# Power_Isolation.net
KiCad netlist of a schematic drawn in Altium Designer
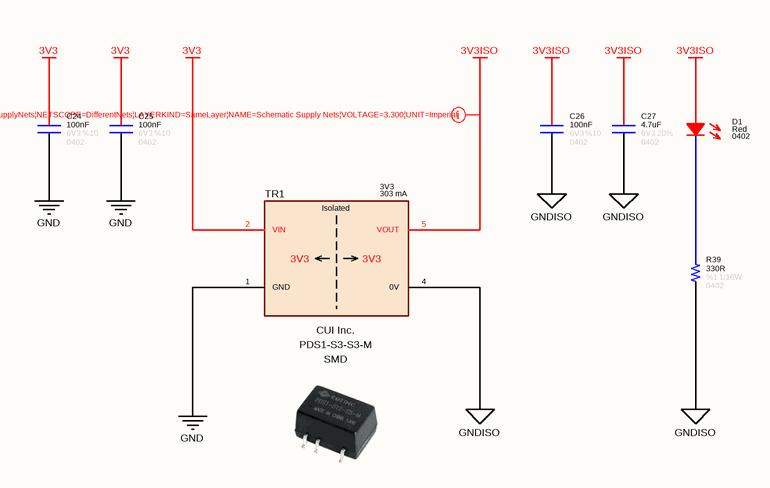
[diagram p0: Power Isolation.SchDoc]

(export (version "E")
  (design (tool "Eeschema 10.0.6"))
  (components
    (comp (ref "C24")
      (value "100nF")
      (footprint "CAPACITOR_0402")
      (description "Capacitor - 100nF [0402-6V3] (Ceramic)")
      (fields
        (field (name "MANUFACTURER PART NUMBER") "04026D104KAT4A")
        (field (name "TOLERANCE") "%10")
        (field (name "VOLTAGE") "6V3")
        (field (name "CASE") "0402")
        (field (name "Comment") "Capacitor - 100nF [0402] (Ceramic)")
      )
      (libsource (lib "Akkoyun") (part "Capacitor - 100nF [0402-6V3]"))
    )
    (comp (ref "C25")
      (value "100nF")
      (footprint "CAPACITOR_0402")
      (description "Capacitor - 100nF [0402-6V3] (Ceramic)")
      (fields
        (field (name "MANUFACTURER PART NUMBER") "04026D104KAT4A")
        (field (name "TOLERANCE") "%10")
        (field (name "VOLTAGE") "6V3")
        (field (name "CASE") "0402")
        (field (name "Comment") "Capacitor - 100nF [0402] (Ceramic)")
      )
      (libsource (lib "Akkoyun") (part "Capacitor - 100nF [0402-6V3]"))
    )
    (comp (ref "C26")
      (value "100nF")
      (footprint "CAPACITOR_0402")
      (description "Capacitor - 100nF [0402-6V3] (Ceramic)")
      (fields
        (field (name "MANUFACTURER PART NUMBER") "04026D104KAT4A")
        (field (name "TOLERANCE") "%10")
        (field (name "VOLTAGE") "6V3")
        (field (name "CASE") "0402")
        (field (name "Comment") "Capacitor - 100nF [0402] (Ceramic)")
      )
      (libsource (lib "Akkoyun") (part "Capacitor - 100nF [0402-6V3]"))
    )
    (comp (ref "C27")
      (value "4.7uF")
      (footprint "CAPACITOR_0402")
      (description "Multilayer Ceramic Capacitors - SMD - 6V3 4.7uF X5R 0402 20%")
      (fields
        (field (name "MANUFACTURER PART NUMBER") "C0402C475M9PACTU")
        (field (name "TOLERANCE") "20%")
        (field (name "CASE") "0402")
        (field (name "VOLTAGE") "6V3")
        (field (name "Comment") "Capacitor - 4.7uF [0402] (Ceramic)")
      )
      (libsource (lib "Akkoyun") (part "Capacitor - 4.7uF [0402-6V3]"))
    )
    (comp (ref "D1")
      (value "SMD LED (Red)")
      (footprint "LED_0402")
      (description "Standard LEDs - SMD MINI-MOLD ULTRA COMPACT RED")
      (fields
        (field (name "MANUFACTURER PART NUMBER") "SML-P12VTT86R")
        (field (name "CASE") "0402")
        (field (name "COLOR") "Red")
      )
      (libsource (lib "Akkoyun") (part "Diode - LED (0402-Red)"))
    )
    (comp (ref "R39")
      (value "330R")
      (footprint "RESISTOR_0402")
      (description "Thick Film Resistors - SMD 1/16 W 330 Ohm 1%")
      (fields
        (field (name "MANUFACTURER PART NUMBER") "CRCW0402330RFKED")
        (field (name "CASE") "0402")
        (field (name "TOLERANCE") "%1")
        (field (name "POWER") "1/16W")
        (field (name "Comment") "330R - 0402 - %1 - 1/16W")
      )
      (libsource (lib "Akkoyun") (part "Resistor - 330R [0402]"))
    )
    (comp (ref "TR1")
      (value "PDS1-S3-S3-M")
      (footprint "PDS1-Sx-Sx-M")
      (description "Module DC-DC 3.3VIN 1-OUT 3.3V 0.303A 1W 5-Pin SMD Module")
      (fields
        (field (name "OUTPUT CURRENT") "303 mA")
        (field (name "OUTPUT VOLTAGE") "3V3")
        (field (name "MANUFACTURER NAME") "CUI Inc.")
        (field (name "MANUFACTURER PART NUMBER") "PDS1-S3-S3-M")
        (field (name "CASE") "SMD")
      )
      (libsource (lib "Akkoyun") (part "Transformator - PDS1-Sx-Sx-M"))
    )
  )
  (nets
    (net (code "1") (name "3V3") (class "Default")
      (node (ref "C24") (pin "2") (pinfunction "2_2") (pintype "passive"))
      (node (ref "C25") (pin "2") (pinfunction "2_2") (pintype "passive"))
      (node (ref "TR1") (pin "2") (pinfunction "VIN_2") (pintype "power_in"))
    )
    (net (code "2") (name "3V3ISO") (class "Default")
      (node (ref "C26") (pin "2") (pinfunction "2_2") (pintype "passive"))
      (node (ref "C27") (pin "2") (pinfunction "2_2") (pintype "passive"))
      (node (ref "D1") (pin "2") (pinfunction "2_2") (pintype "passive"))
      (node (ref "TR1") (pin "5") (pinfunction "VOUT_5") (pintype "power_in"))
    )
    (net (code "3") (name "GND") (class "Default")
      (node (ref "C24") (pin "1") (pinfunction "1_1") (pintype "passive"))
      (node (ref "C25") (pin "1") (pinfunction "1_1") (pintype "passive"))
      (node (ref "TR1") (pin "1") (pinfunction "GND_1") (pintype "power_in"))
    )
    (net (code "4") (name "GNDISO") (class "Default")
      (node (ref "C26") (pin "1") (pinfunction "1_1") (pintype "passive"))
      (node (ref "C27") (pin "1") (pinfunction "1_1") (pintype "passive"))
      (node (ref "R39") (pin "1") (pinfunction "1_1") (pintype "passive"))
      (node (ref "TR1") (pin "4") (pinfunction "0V_4") (pintype "power_in"))
    )
    (net (code "5") (name "Net-(D1-Pad1)") (class "Default")
      (node (ref "D1") (pin "1") (pinfunction "1_1") (pintype "passive"))
      (node (ref "R39") (pin "2") (pinfunction "2_2") (pintype "passive"))
    )
    (net (code "6") (name "unconnected-(TR1-Terminator-Pad8)") (class "Default")
      (node (ref "TR1") (pin "8") (pinfunction "Terminator_8") (pintype "passive"))
    )
  )
)
